# boltanka.net
KiCad netlist of a schematic drawn in Altium Designer
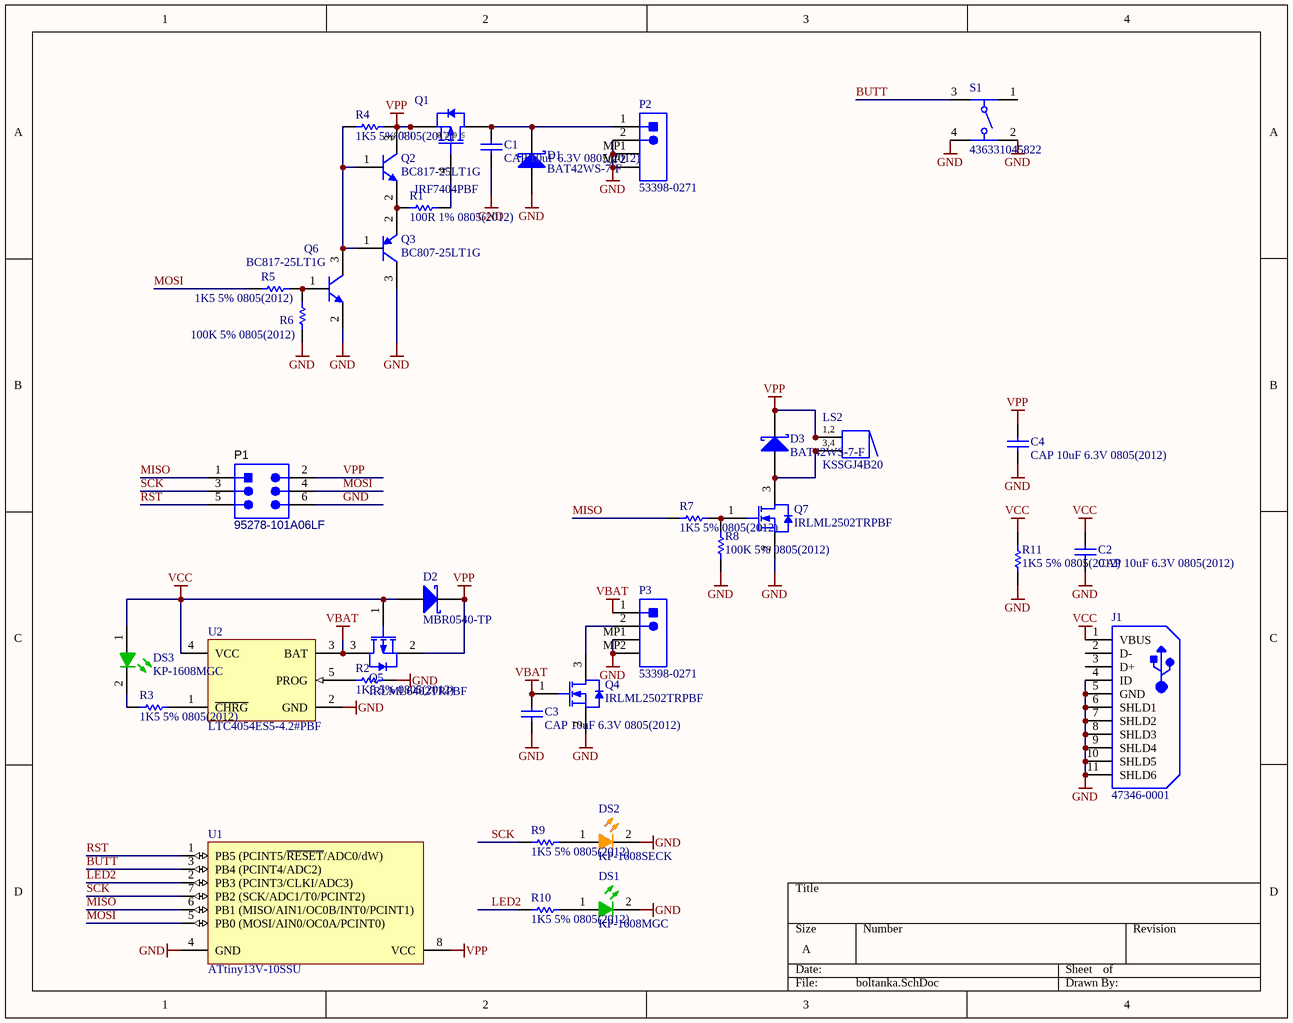
[diagram p0: boltanka.SchDoc]

(export (version "E")
  (design (tool "Eeschema 10.0.6"))
  (components
    (comp (ref "C1")
      (value "CAP 10uF 6.3V 0805(2012)")
      (footprint "CAPC0805(2012)100_L")
      (description "CAP 10uF 6.3V ±10% 0805 (2012 Metric) Thickness 1mm SMD")
      (fields (field (name "TOLERANCE") "Â±10%"))
      (libsource (lib "Altium Content Vault") (part "CAP"))
    )
    (comp (ref "C2")
      (value "CAP 10uF 6.3V 0805(2012)")
      (footprint "CAPC0805(2012)100_L")
      (description "CAP 10uF 6.3V ±10% 0805 (2012 Metric) Thickness 1mm SMD")
      (fields (field (name "TOLERANCE") "Â±10%"))
      (libsource (lib "Altium Content Vault") (part "CAP"))
    )
    (comp (ref "C3")
      (value "CAP 10uF 6.3V 0805(2012)")
      (footprint "CAPC0805(2012)100_L")
      (description "CAP 10uF 6.3V ±10% 0805 (2012 Metric) Thickness 1mm SMD")
      (fields (field (name "TOLERANCE") "Â±10%"))
      (libsource (lib "Altium Content Vault") (part "CAP"))
    )
    (comp (ref "C4")
      (value "CAP 10uF 6.3V 0805(2012)")
      (footprint "CAPC0805(2012)100_L")
      (description "CAP 10uF 6.3V ±10% 0805 (2012 Metric) Thickness 1mm SMD")
      (fields (field (name "TOLERANCE") "Â±10%"))
      (libsource (lib "Altium Content Vault") (part "CAP"))
    )
    (comp (ref "D1")
      (value "BAT42WS-7-F")
      (footprint "DIOD-SOD323-2_V")
      (description "Schottky Barrier Diode, 30 V, -55 to 125 degC, 2-Pin SOD323, RoHS, Tape and Reel")
      (fields (field (name "MANUFACTURER") "DiodesIncorporated"))
      (libsource (lib "Altium Content Vault") (part "DSKY-AK-2"))
    )
    (comp (ref "D2")
      (value "MBR0540-TP")
      (footprint "MCC-SOD123_V")
      (description "Schottky Rectifier, 0.5 A, 40 V, -55 to 150 degC, 2-Pin SOD123, Pb-Free, Tape and Reel")
      (fields (field (name "MANUFACTURER") "Micro Commercial Components"))
      (libsource (lib "Altium Content Vault") (part "DSKY-AK-2"))
    )
    (comp (ref "D3")
      (value "BAT42WS-7-F")
      (footprint "DIOD-SOD323-2_V")
      (description "Schottky Barrier Diode, 30 V, -55 to 125 degC, 2-Pin SOD323, RoHS, Tape and Reel")
      (fields (field (name "MANUFACTURER") "DiodesIncorporated"))
      (libsource (lib "Altium Content Vault") (part "DSKY-AK-2"))
    )
    (comp (ref "DS1")
      (value "KP-1608MGC")
      (footprint "KING-0603LED_GREEN_V")
      (description "LED, SMT, 0603(1608), 1.1mm thickness, Green")
      (fields (field (name "MANUFACTURER") "Kingbright"))
      (libsource (lib "Altium Content Vault") (part "KING-LED-GREEN-A1K2-2"))
    )
    (comp (ref "DS2")
      (value "KP-1608SECK")
      (footprint "KING-0603LED_ORANGE_V")
      (description "LED, SMT, 0603(1608), 1.1mm thickness, Orange")
      (fields (field (name "MANUFACTURER") "Kingbright"))
      (libsource (lib "Altium Content Vault") (part "KING-LED-ORANGE-A1K2-2"))
    )
    (comp (ref "DS3")
      (value "KP-1608MGC")
      (footprint "KING-0603LED_GREEN_V")
      (description "LED, SMT, 0603(1608), 1.1mm thickness, Green")
      (fields (field (name "MANUFACTURER") "Kingbright"))
      (libsource (lib "Altium Content Vault") (part "KING-LED-GREEN-A1K2-2"))
    )
    (comp (ref "J1")
      (value "47346-0001")
      (footprint "MOLX-47346-0001-5_V")
      (description "Micro-USB B Receptacle with Flange, -30 to 85 degC, 5-Pin SMD, RoHS, Tape and Reel")
      (fields (field (name "MANUFACTURER") "Molex"))
      (libsource (lib "Altium Content Vault") (part "MOLX-47346-0001-5"))
    )
    (comp (ref "LS2")
      (value "KSSGJ4B20")
      (footprint "KINGS-KSSGJ4B20_V")
      (description "Electromagnetic Buzzer, 3 to 5 V, 80 mA, 2.73 kHz, -30 to 70 degC, 4-Pin SMD, RoHS, Tape and Reel")
      (fields (field (name "MANUFACTURER") "KingstateElectronicsCorp."))
      (libsource (lib "Altium Content Vault") (part "KINGS-KSSGJ4B20"))
    )
    (comp (ref "P1")
      (value "95278-101A06LF")
      (footprint "AMPM-95278-101A06LF_V")
      (description "Male Header, Pitch 2.54 mm, 2 x 3 Position, Height 14.4 mm, RoHS, Tape and Reel")
      (fields (field (name "TOLERANCE") "1%"))
      (libsource (lib "Altium Content Vault") (part "CN-2P-M-R6"))
    )
    (comp (ref "P2")
      (value "53398-0271")
      (footprint "MOLX-53398-0271_V")
      (description "Male Header, Pitch 1.25 mm, 1 x 2 Position, Height 4.7 mm, -40 to 85 degC, RoHS, Tape and Reel")
      (fields (field (name "MANUFACTURER") "Molex"))
      (libsource (lib "Altium Content Vault") (part "CN-1P-2M-R2"))
    )
    (comp (ref "P3")
      (value "53398-0271")
      (footprint "MOLX-53398-0271_V")
      (description "Male Header, Pitch 1.25 mm, 1 x 2 Position, Height 4.7 mm, -40 to 85 degC, RoHS, Tape and Reel")
      (fields (field (name "MANUFACTURER") "Molex"))
      (libsource (lib "Altium Content Vault") (part "CN-1P-2M-R2"))
    )
    (comp (ref "Q1")
      (value "IRF7404PBF")
      (footprint "INF-SOIC-8_V")
      (description "HEXFET(R) Power MOSFET, 6.7 A, 20 V, 8-Pin SOIC, RoHS, Tape and Reel")
      (fields (field (name "MANUFACTURER") "InfineonTechnologies"))
      (libsource (lib "Altium Content Vault") (part "PEMOS-SSSGDDDD-8"))
    )
    (comp (ref "Q2")
      (value "BC817-25LT1G")
      (footprint "ONSC-SOT-23-3-318-08_V")
      (description "General Purpose Transistor, NPN Silicon, 3-Pin SOT-23, Pb-Free, Tape and Reel")
      (fields (field (name "MANUFACTURER") "On Semiconductor"))
      (libsource (lib "Altium Content Vault") (part "ONSC-NPN-B1E2C3-3"))
    )
    (comp (ref "Q3")
      (value "BC807-25LT1G")
      (footprint "ONSC-SOT-23-3-318-08_V")
      (description "General Purpose Transistor, PNP Silicon, 3-Pin SOT-23, Pb-Free, Tape and Reel")
      (fields (field (name "MANUFACTURER") "On Semiconductor"))
      (libsource (lib "Altium Content Vault") (part "ONSC-PNP-B1E2C3-3"))
    )
    (comp (ref "Q4")
      (value "IRLML2502TRPBF")
      (footprint "INTR-SOT-23-3_V")
      (description "N-Channel HEXFET(R) Power MOSFET, 20 V VDS, +/- 12 V VGS, 4.2 A, 3-Pin SOT23, RoHS, Tape and Reel")
      (fields (field (name "MANUFACTURER") "International Rectifier"))
      (libsource (lib "Altium Content Vault") (part "NEMOS-GSD-3"))
    )
    (comp (ref "Q5")
      (value "IRLML6402TRPBF")
      (footprint "INTR-SOT-23-3_V")
      (fields (field (name "MANUFACTURER") "International Rectifier"))
      (libsource (lib "Altium Content Vault") (part "PEMOS-GSD-3"))
    )
    (comp (ref "Q6")
      (value "BC817-25LT1G")
      (footprint "ONSC-SOT-23-3-318-08_V")
      (description "General Purpose Transistor, NPN Silicon, 3-Pin SOT-23, Pb-Free, Tape and Reel")
      (fields (field (name "MANUFACTURER") "On Semiconductor"))
      (libsource (lib "Altium Content Vault") (part "ONSC-NPN-B1E2C3-3"))
    )
    (comp (ref "Q7")
      (value "IRLML2502TRPBF")
      (footprint "INTR-SOT-23-3_V")
      (description "N-Channel HEXFET(R) Power MOSFET, 20 V VDS, +/- 12 V VGS, 4.2 A, 3-Pin SOT23, RoHS, Tape and Reel")
      (fields (field (name "MANUFACTURER") "International Rectifier"))
      (libsource (lib "Altium Content Vault") (part "NEMOS-GSD-3"))
    )
    (comp (ref "R1")
      (value "100R 1% 0805(2012)")
      (footprint "RESC0805(2012)_L")
      (description "100R 0.125W 1% 0805 (2012 Metric)  SMD")
      (fields (field (name "POWER") "0.125 W") (field (name "TOLERANCE") "1 %"))
      (libsource (lib "Altium Content Vault") (part "RES"))
    )
    (comp (ref "R2")
      (value "1K5 5% 0805(2012)")
      (footprint "RESC0805(2012)_L")
      (description "1K5 0.125W 5% 0805 (2012 Metric)  SMD")
      (fields (field (name "POWER") "0.125 W") (field (name "TOLERANCE") "5 %"))
      (libsource (lib "Altium Content Vault") (part "RES"))
    )
    (comp (ref "R3")
      (value "1K5 5% 0805(2012)")
      (footprint "RESC0805(2012)_L")
      (description "1K5 0.125W 5% 0805 (2012 Metric)  SMD")
      (fields (field (name "POWER") "0.125 W") (field (name "TOLERANCE") "5 %"))
      (libsource (lib "Altium Content Vault") (part "RES"))
    )
    (comp (ref "R4")
      (value "1K5 5% 0805(2012)")
      (footprint "RESC0805(2012)_L")
      (description "1K5 0.125W 5% 0805 (2012 Metric)  SMD")
      (fields (field (name "POWER") "0.125 W") (field (name "TOLERANCE") "5 %"))
      (libsource (lib "Altium Content Vault") (part "RES"))
    )
    (comp (ref "R5")
      (value "1K5 5% 0805(2012)")
      (footprint "RESC0805(2012)_L")
      (description "1K5 0.125W 5% 0805 (2012 Metric)  SMD")
      (fields (field (name "POWER") "0.125 W") (field (name "TOLERANCE") "5 %"))
      (libsource (lib "Altium Content Vault") (part "RES"))
    )
    (comp (ref "R6")
      (value "100K 5% 0805(2012)")
      (footprint "RESC0805(2012)_L")
      (description "100K 0.125W 5% 0805 (2012 Metric)  SMD")
      (fields (field (name "TOLERANCE") "5 %") (field (name "POWER") "0.125 W"))
      (libsource (lib "Altium Content Vault") (part "RES"))
    )
    (comp (ref "R7")
      (value "1K5 5% 0805(2012)")
      (footprint "RESC0805(2012)_L")
      (description "1K5 0.125W 5% 0805 (2012 Metric)  SMD")
      (fields (field (name "POWER") "0.125 W") (field (name "TOLERANCE") "5 %"))
      (libsource (lib "Altium Content Vault") (part "RES"))
    )
    (comp (ref "R8")
      (value "100K 5% 0805(2012)")
      (footprint "RESC0805(2012)_L")
      (description "100K 0.125W 5% 0805 (2012 Metric)  SMD")
      (fields (field (name "TOLERANCE") "5 %") (field (name "POWER") "0.125 W"))
      (libsource (lib "Altium Content Vault") (part "RES"))
    )
    (comp (ref "R9")
      (value "1K5 5% 0805(2012)")
      (footprint "RESC0805(2012)_L")
      (description "1K5 0.125W 5% 0805 (2012 Metric)  SMD")
      (fields (field (name "POWER") "0.125 W") (field (name "TOLERANCE") "5 %"))
      (libsource (lib "Altium Content Vault") (part "RES"))
    )
    (comp (ref "R10")
      (value "1K5 5% 0805(2012)")
      (footprint "RESC0805(2012)_L")
      (description "1K5 0.125W 5% 0805 (2012 Metric)  SMD")
      (fields (field (name "POWER") "0.125 W") (field (name "TOLERANCE") "5 %"))
      (libsource (lib "Altium Content Vault") (part "RES"))
    )
    (comp (ref "R11")
      (value "1K5 5% 0805(2012)")
      (footprint "RESC0805(2012)_L")
      (description "1K5 0.125W 5% 0805 (2012 Metric)  SMD")
      (fields (field (name "POWER") "0.125 W") (field (name "TOLERANCE") "5 %"))
      (libsource (lib "Altium Content Vault") (part "RES"))
    )
    (comp (ref "S1")
      (value "436331045822")
      (footprint "4363x10458xx")
      (description "WS-TASU 3.5x4.7 mm SMD side push, boss design")
      (fields (field (name "PUBLISHER") "Wurth Elektronik"))
      (libsource (lib "ALTIUM-WS-TASU-rev17a") (part "436331045822"))
    )
    (comp (ref "U1")
      (value "ATtiny13V-10SSU")
      (footprint "S8S1_M")
      (libsource (lib "Altium Content Vault") (part "MC-8B-ATT13A-IL8"))
    )
    (comp (ref "U2")
      (value "LTC4054ES5-4.2#PBF")
      (footprint "LT-S5-5-TSOT-23_M")
      (fields (field (name "MANUFACTURER") "Linear Technology"))
      (libsource (lib "Altium Content Vault") (part "LT-LTC4054-S5-5"))
    )
  )
  (nets
    (net (code "1") (name "/BUTT") (class "Default")
      (node (ref "S1") (pin "3") (pinfunction "3_3") (pintype "passive"))
      (node (ref "U1") (pin "3") (pinfunction "PB4_(PCINT4/ADC2)_3") (pintype "bidirectional"))
    )
    (net (code "2") (name "/LED2") (class "Default")
      (node (ref "R10") (pin "1") (pinfunction "1_1") (pintype "passive"))
      (node (ref "U1") (pin "2") (pinfunction "PB3_(PCINT3/CLKI/ADC3)_2") (pintype "bidirectional"))
    )
    (net (code "3") (name "/MISO") (class "Default")
      (node (ref "P1") (pin "1") (pinfunction "1_1") (pintype "passive"))
      (node (ref "R7") (pin "1") (pinfunction "1_1") (pintype "passive"))
      (node (ref "U1") (pin "6") (pinfunction "PB1_(MISO/AIN1/OC0B/INT0/PCINT1)_6") (pintype "bidirectional"))
    )
    (net (code "4") (name "/MOSI") (class "Default")
      (node (ref "P1") (pin "4") (pinfunction "4_4") (pintype "passive"))
      (node (ref "R5") (pin "1") (pinfunction "1_1") (pintype "passive"))
      (node (ref "U1") (pin "5") (pinfunction "PB0_(MOSI/AIN0/OC0A/PCINT0)_5") (pintype "bidirectional"))
    )
    (net (code "5") (name "/RST") (class "Default")
      (node (ref "P1") (pin "5") (pinfunction "5_5") (pintype "passive"))
      (node (ref "U1") (pin "1") (pinfunction "PB5_(PCINT5/~{RESET}/ADC0/dW)_1") (pintype "bidirectional"))
    )
    (net (code "6") (name "/SCK") (class "Default")
      (node (ref "P1") (pin "3") (pinfunction "3_3") (pintype "passive"))
      (node (ref "R9") (pin "1") (pinfunction "1_1") (pintype "passive"))
      (node (ref "U1") (pin "7") (pinfunction "PB2_(SCK/ADC1/T0/PCINT2)_7") (pintype "bidirectional"))
    )
    (net (code "7") (name "GND") (class "Default")
      (node (ref "C1") (pin "1") (pinfunction "1_1") (pintype "passive"))
      (node (ref "C2") (pin "1") (pinfunction "1_1") (pintype "passive"))
      (node (ref "C3") (pin "1") (pinfunction "1_1") (pintype "passive"))
      (node (ref "C4") (pin "1") (pinfunction "1_1") (pintype "passive"))
      (node (ref "D1") (pin "1") (pinfunction "A_1") (pintype "passive"))
      (node (ref "DS1") (pin "2") (pinfunction "K_2") (pintype "passive"))
      (node (ref "DS2") (pin "2") (pinfunction "K_2") (pintype "passive"))
      (node (ref "J1") (pin "10") (pinfunction "SHLD5_10") (pintype "passive"))
      (node (ref "J1") (pin "11") (pinfunction "SHLD6_11") (pintype "passive"))
      (node (ref "J1") (pin "4") (pinfunction "ID_4") (pintype "passive"))
      (node (ref "J1") (pin "5") (pinfunction "GND_5") (pintype "passive"))
      (node (ref "J1") (pin "6") (pinfunction "SHLD1_6") (pintype "passive"))
      (node (ref "J1") (pin "7") (pinfunction "SHLD2_7") (pintype "passive"))
      (node (ref "J1") (pin "8") (pinfunction "SHLD3_8") (pintype "passive"))
      (node (ref "J1") (pin "9") (pinfunction "SHLD4_9") (pintype "passive"))
      (node (ref "P1") (pin "6") (pinfunction "6_6") (pintype "passive"))
      (node (ref "P2") (pin "2") (pinfunction "2_2") (pintype "passive"))
      (node (ref "P2") (pin "MP1") (pinfunction "MP1_MP1") (pintype "passive"))
      (node (ref "P2") (pin "MP2") (pinfunction "MP2_MP2") (pintype "passive"))
      (node (ref "P3") (pin "MP1") (pinfunction "MP1_MP1") (pintype "passive"))
      (node (ref "P3") (pin "MP2") (pinfunction "MP2_MP2") (pintype "passive"))
      (node (ref "Q3") (pin "3") (pinfunction "C_3") (pintype "passive"))
      (node (ref "Q4") (pin "2") (pinfunction "S_2") (pintype "passive"))
      (node (ref "Q6") (pin "2") (pinfunction "E_2") (pintype "passive"))
      (node (ref "Q7") (pin "2") (pinfunction "S_2") (pintype "passive"))
      (node (ref "R11") (pin "1") (pinfunction "1_1") (pintype "passive"))
      (node (ref "R2") (pin "2") (pinfunction "2_2") (pintype "passive"))
      (node (ref "R6") (pin "1") (pinfunction "1_1") (pintype "passive"))
      (node (ref "R8") (pin "1") (pinfunction "1_1") (pintype "passive"))
      (node (ref "S1") (pin "2") (pinfunction "2_2") (pintype "passive"))
      (node (ref "S1") (pin "4") (pinfunction "4_4") (pintype "passive"))
      (node (ref "U1") (pin "4") (pinfunction "GND_4") (pintype "power_in"))
      (node (ref "U2") (pin "2") (pinfunction "GND_2") (pintype "power_in"))
    )
    (net (code "8") (name "Net-(D1-K)") (class "Default")
      (node (ref "C1") (pin "2") (pinfunction "2_2") (pintype "passive"))
      (node (ref "D1") (pin "2") (pinfunction "K_2") (pintype "passive"))
      (node (ref "P2") (pin "1") (pinfunction "1_1") (pintype "passive"))
      (node (ref "Q1") (pin "5") (pinfunction "D_5") (pintype "passive"))
      (node (ref "Q1") (pin "6") (pinfunction "D_6") (pintype "passive"))
      (node (ref "Q1") (pin "7") (pinfunction "D_7") (pintype "passive"))
      (node (ref "Q1") (pin "8") (pinfunction "D_8") (pintype "passive"))
    )
    (net (code "9") (name "Net-(D3-A)") (class "Default")
      (node (ref "D3") (pin "1") (pinfunction "A_1") (pintype "passive"))
      (node (ref "LS2") (pin "3") (pinfunction "3_3") (pintype "passive"))
      (node (ref "LS2") (pin "4") (pinfunction "4_4") (pintype "passive"))
      (node (ref "Q7") (pin "3") (pinfunction "D_3") (pintype "passive"))
    )
    (net (code "10") (name "Net-(DS1-A)") (class "Default")
      (node (ref "DS1") (pin "1") (pinfunction "A_1") (pintype "passive"))
      (node (ref "R10") (pin "2") (pinfunction "2_2") (pintype "passive"))
    )
    (net (code "11") (name "Net-(DS2-A)") (class "Default")
      (node (ref "DS2") (pin "1") (pinfunction "A_1") (pintype "passive"))
      (node (ref "R9") (pin "2") (pinfunction "2_2") (pintype "passive"))
    )
    (net (code "12") (name "Net-(DS3-K)") (class "Default")
      (node (ref "DS3") (pin "2") (pinfunction "K_2") (pintype "passive"))
      (node (ref "R3") (pin "1") (pinfunction "1_1") (pintype "passive"))
    )
    (net (code "13") (name "Net-(Q1-G)") (class "Default")
      (node (ref "Q1") (pin "4") (pinfunction "G_4") (pintype "passive"))
      (node (ref "R1") (pin "2") (pinfunction "2_2") (pintype "passive"))
    )
    (net (code "14") (name "Net-(Q2-B)") (class "Default")
      (node (ref "Q2") (pin "1") (pinfunction "B_1") (pintype "passive"))
      (node (ref "Q3") (pin "1") (pinfunction "B_1") (pintype "passive"))
      (node (ref "Q6") (pin "3") (pinfunction "C_3") (pintype "passive"))
      (node (ref "R4") (pin "1") (pinfunction "1_1") (pintype "passive"))
    )
    (net (code "15") (name "Net-(Q2-E)") (class "Default")
      (node (ref "Q2") (pin "2") (pinfunction "E_2") (pintype "passive"))
      (node (ref "Q3") (pin "2") (pinfunction "E_2") (pintype "passive"))
      (node (ref "R1") (pin "1") (pinfunction "1_1") (pintype "passive"))
    )
    (net (code "16") (name "Net-(Q4-D)") (class "Default")
      (node (ref "P3") (pin "2") (pinfunction "2_2") (pintype "passive"))
      (node (ref "Q4") (pin "3") (pinfunction "D_3") (pintype "passive"))
    )
    (net (code "17") (name "Net-(Q6-B)") (class "Default")
      (node (ref "Q6") (pin "1") (pinfunction "B_1") (pintype "passive"))
      (node (ref "R5") (pin "2") (pinfunction "2_2") (pintype "passive"))
      (node (ref "R6") (pin "2") (pinfunction "2_2") (pintype "passive"))
    )
    (net (code "18") (name "Net-(Q7-G)") (class "Default")
      (node (ref "Q7") (pin "1") (pinfunction "G_1") (pintype "passive"))
      (node (ref "R7") (pin "2") (pinfunction "2_2") (pintype "passive"))
      (node (ref "R8") (pin "2") (pinfunction "2_2") (pintype "passive"))
    )
    (net (code "19") (name "Net-(U2-PROG)") (class "Default")
      (node (ref "R2") (pin "1") (pinfunction "1_1") (pintype "passive"))
      (node (ref "U2") (pin "5") (pinfunction "PROG_5") (pintype "input"))
    )
    (net (code "20") (name "Net-(U2-~{CHRG})") (class "Default")
      (node (ref "R3") (pin "2") (pinfunction "2_2") (pintype "passive"))
      (node (ref "U2") (pin "1") (pinfunction "~{CHRG}_1") (pintype "tri_state"))
    )
    (net (code "21") (name "VBAT") (class "Default")
      (node (ref "C3") (pin "2") (pinfunction "2_2") (pintype "passive"))
      (node (ref "P3") (pin "1") (pinfunction "1_1") (pintype "passive"))
      (node (ref "Q4") (pin "1") (pinfunction "G_1") (pintype "passive"))
      (node (ref "Q5") (pin "3") (pinfunction "DRAIN_3") (pintype "passive"))
      (node (ref "U2") (pin "3") (pinfunction "BAT_3") (pintype "power_in"))
    )
    (net (code "22") (name "VCC") (class "Default")
      (node (ref "C2") (pin "2") (pinfunction "2_2") (pintype "passive"))
      (node (ref "D2") (pin "1") (pinfunction "A_1") (pintype "passive"))
      (node (ref "DS3") (pin "1") (pinfunction "A_1") (pintype "passive"))
      (node (ref "J1") (pin "1") (pinfunction "VBUS_1") (pintype "passive"))
      (node (ref "Q5") (pin "1") (pinfunction "GATE_1") (pintype "passive"))
      (node (ref "R11") (pin "2") (pinfunction "2_2") (pintype "passive"))
      (node (ref "U2") (pin "4") (pinfunction "VCC_4") (pintype "power_in"))
    )
    (net (code "23") (name "VPP") (class "Default")
      (node (ref "C4") (pin "2") (pinfunction "2_2") (pintype "passive"))
      (node (ref "D2") (pin "2") (pinfunction "K_2") (pintype "passive"))
      (node (ref "D3") (pin "2") (pinfunction "K_2") (pintype "passive"))
      (node (ref "LS2") (pin "1") (pinfunction "1_1") (pintype "passive"))
      (node (ref "LS2") (pin "2") (pinfunction "2_2") (pintype "passive"))
      (node (ref "P1") (pin "2") (pinfunction "2_2") (pintype "passive"))
      (node (ref "Q1") (pin "1") (pinfunction "S_1") (pintype "passive"))
      (node (ref "Q1") (pin "2") (pinfunction "S_2") (pintype "passive"))
      (node (ref "Q1") (pin "3") (pinfunction "S_3") (pintype "passive"))
      (node (ref "Q2") (pin "3") (pinfunction "C_3") (pintype "passive"))
      (node (ref "Q5") (pin "2") (pinfunction "SOURCE_2") (pintype "passive"))
      (node (ref "R4") (pin "2") (pinfunction "2_2") (pintype "passive"))
      (node (ref "U1") (pin "8") (pinfunction "VCC_8") (pintype "power_in"))
    )
    (net (code "24") (name "unconnected-(J1-D+-Pad3)") (class "Default")
      (node (ref "J1") (pin "3") (pinfunction "D+_3") (pintype "passive"))
    )
    (net (code "25") (name "unconnected-(J1-D--Pad2)") (class "Default")
      (node (ref "J1") (pin "2") (pinfunction "D-_2") (pintype "passive"))
    )
    (net (code "26") (name "unconnected-(S1-Pad1)") (class "Default")
      (node (ref "S1") (pin "1") (pinfunction "1_1") (pintype "passive"))
    )
  )
)
